# ESP8266.net
KiCad netlist of a schematic drawn in Altium Designer
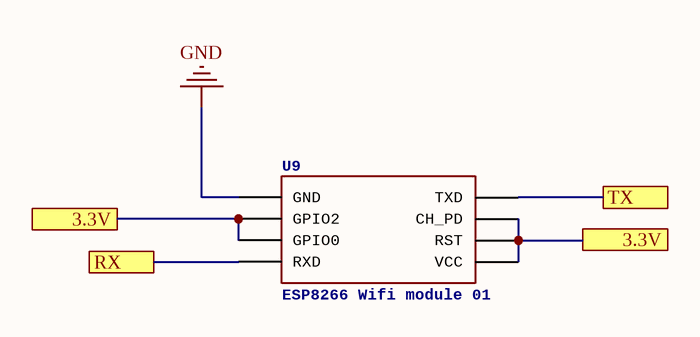
[diagram p0: ESP8266.SchDoc]

(export (version "E")
  (design (tool "Eeschema 10.0.6"))
  (components
    (comp (ref "U9")
      (value "ESP8266 Wifi module 01")
      (footprint "ESP01")
      (libsource (lib "esp8266modules") (part "ESP01"))
    )
  )
  (nets
    (net (code "1") (name "/3.3V") (class "Default")
      (node (ref "U9") (pin "CH_PD") (pinfunction "CH_PD_CH_PD") (pintype "passive"))
      (node (ref "U9") (pin "GPIO0") (pinfunction "GPIO0_GPIO0") (pintype "passive"))
      (node (ref "U9") (pin "GPIO2") (pinfunction "GPIO2_GPIO2") (pintype "passive"))
      (node (ref "U9") (pin "RST") (pinfunction "RST_RST") (pintype "passive"))
      (node (ref "U9") (pin "VCC") (pinfunction "VCC_VCC") (pintype "passive"))
    )
    (net (code "2") (name "/RX") (class "Default")
      (node (ref "U9") (pin "RX") (pinfunction "RXD_RX") (pintype "passive"))
    )
    (net (code "3") (name "/TX") (class "Default")
      (node (ref "U9") (pin "TX") (pinfunction "TXD_TX") (pintype "passive"))
    )
    (net (code "4") (name "GND") (class "Default")
      (node (ref "U9") (pin "GND") (pinfunction "GND_GND") (pintype "passive"))
    )
  )
)
